# Sheet1.net
KiCad netlist of a schematic drawn in Altium Designer
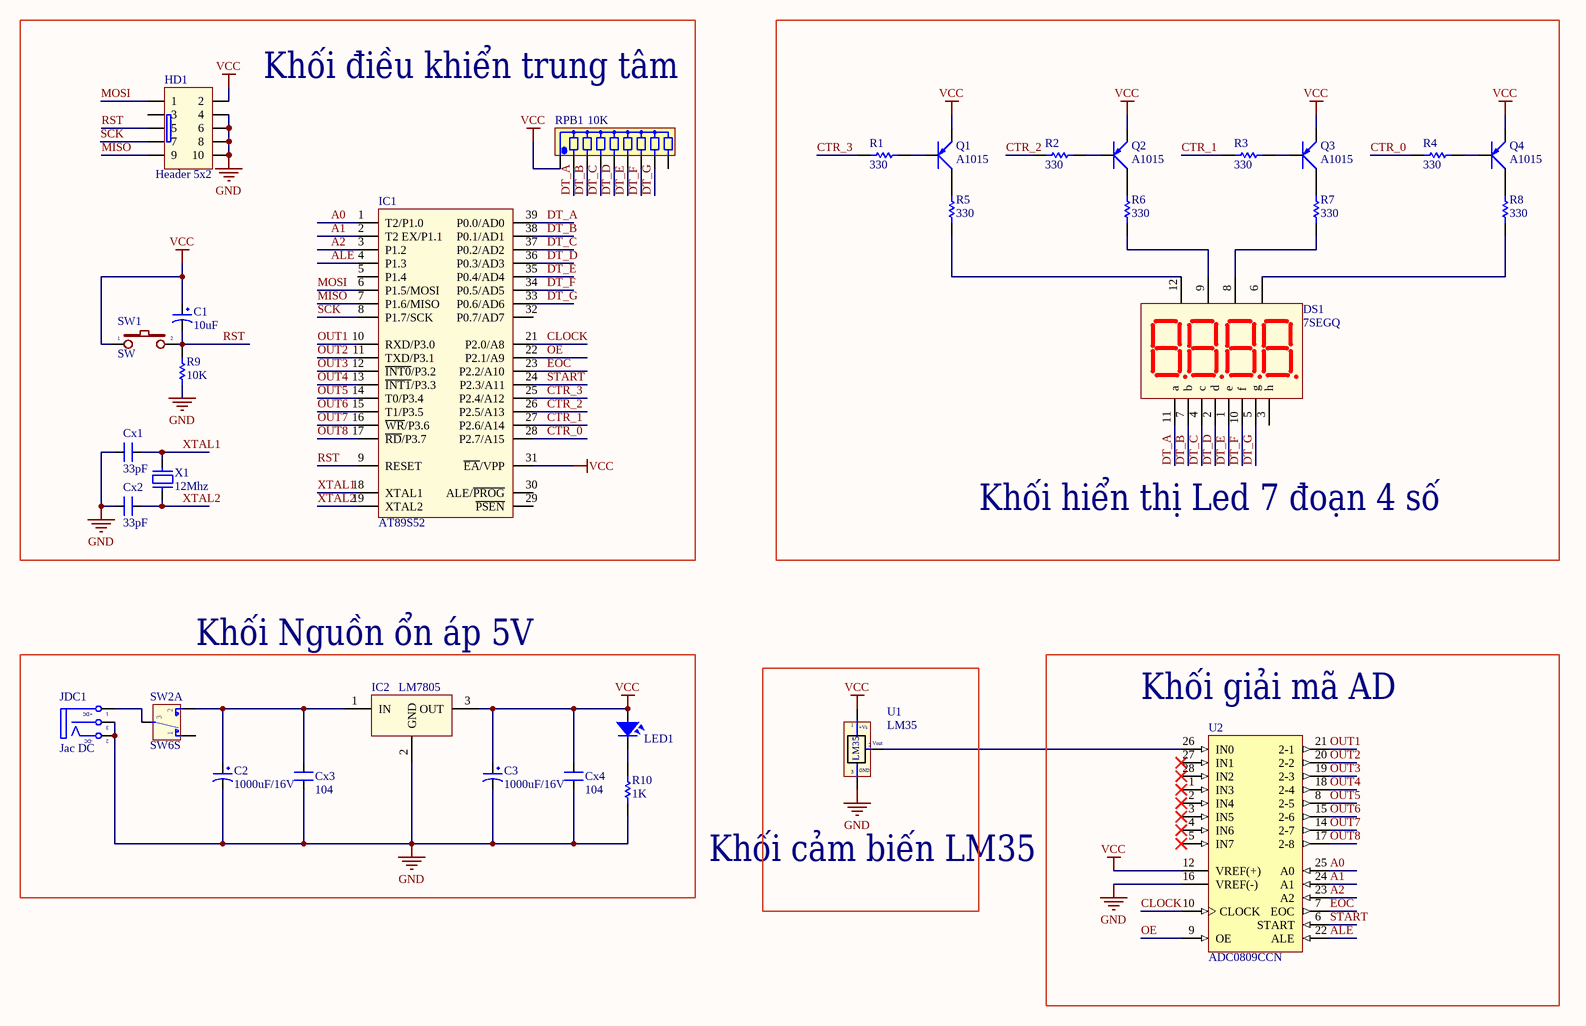
[diagram p0: Sheet1.SchDoc]

(export (version "E")
  (design (tool "Eeschema 10.0.6"))
  (components
    (comp (ref "C1")
      (value "10uF")
      (footprint "CP1/2")
      (description "Cap P  0,1uF < 22uF , 16 - 50V")
      (libsource (lib "DEV_lib") (part "Cap 0,1uF-{gt}22uF"))
    )
    (comp (ref "C2")
      (value "1000uF/16V")
      (footprint "CP1.5/3.4")
      (description "Cap 1000uF/16V - 220uF/50V")
      (libsource (lib "syhaunguyen") (part "CP4"))
    )
    (comp (ref "C3")
      (value "1000uF/16V")
      (footprint "CP1.5/3.4")
      (description "Cap 1000uF/16V - 220uF/50V")
      (libsource (lib "syhaunguyen") (part "CP4"))
    )
    (comp (ref "Cx1")
      (value "33pF")
      (footprint "CN1")
      (description "Cremic For Xtal 1pF => 100pF")
      (libsource (lib "syhaunguyen") (part "CN0"))
    )
    (comp (ref "Cx2")
      (value "33pF")
      (footprint "CN1")
      (description "Cremic For Xtal 1pF => 100pF")
      (libsource (lib "syhaunguyen") (part "CN0"))
    )
    (comp (ref "Cx3") (value "104") (footprint "CN1") (libsource (lib "LIBRARY") (part "CN")))
    (comp (ref "Cx4") (value "104") (footprint "CN1") (libsource (lib "LIBRARY") (part "CN")))
    (comp (ref "DS1")
      (value "7SEGQ")
      (footprint "LED7SEG-4-0.36")
      (description "Four 7 Seg Dipslay")
      (libsource (lib "DEV_lib") (part "LED7SEG-4"))
    )
    (comp (ref "HD1") (value "Header 5x2") (footprint "Hed2X5") (libsource (lib "DEV_lib") (part "HED5x2")))
    (comp (ref "IC1")
      (value "AT89S52")
      (footprint "DIP40/W0.6")
      (description "AT89S52, 8k Byte Flash Memory , 40 Pin")
      (libsource (lib "LIBRARY") (part "AT89S52"))
    )
    (comp (ref "IC2")
      (value "LM7805")
      (footprint "QTO-220")
      (description "On ap +, from + 5 to + 24VDC")
      (libsource (lib "DEV_lib") (part "LM78xx"))
    )
    (comp (ref "JDC1")
      (value "Jac DC")
      (footprint "DC-IN")
      (description "Jac DC input")
      (libsource (lib "syhaunguyen") (part "DCIN"))
    )
    (comp (ref "LED1")
      (value "LED")
      (footprint "LED-5-RED")
      (description "LED Single colour Green and Red")
      (libsource (lib "syhaunguyen") (part "LED"))
    )
    (comp (ref "Q1")
      (value "A1015")
      (footprint "QTO-92")
      (description "PNP 600mW, ECB")
      (libsource (lib "DEV_lib") (part "A1015"))
    )
    (comp (ref "Q2")
      (value "A1015")
      (footprint "QTO-92")
      (description "PNP 600mW, ECB")
      (libsource (lib "DEV_lib") (part "A1015"))
    )
    (comp (ref "Q3")
      (value "A1015")
      (footprint "QTO-92")
      (description "PNP 600mW, ECB")
      (libsource (lib "DEV_lib") (part "A1015"))
    )
    (comp (ref "Q4")
      (value "A1015")
      (footprint "QTO-92")
      (description "PNP 600mW, ECB")
      (libsource (lib "DEV_lib") (part "A1015"))
    )
    (comp (ref "R1")
      (value "330")
      (footprint "R1/4W")
      (description "Resistor")
      (fields
        (field (name "MANUFACTURER") "Generic Components")
        (field (name "Comment") "Res1")
        (field (name "PUBLISHER") "Altium Hobart Technology Centre")
      )
      (libsource (lib "DEV_lib") (part "Res1_4"))
    )
    (comp (ref "R2")
      (value "330")
      (footprint "R1/4W")
      (description "Resistor")
      (fields
        (field (name "MANUFACTURER") "Generic Components")
        (field (name "Comment") "Res1")
        (field (name "PUBLISHER") "Altium Hobart Technology Centre")
      )
      (libsource (lib "DEV_lib") (part "Res1_4"))
    )
    (comp (ref "R3")
      (value "330")
      (footprint "R1/4W")
      (description "Resistor")
      (fields
        (field (name "MANUFACTURER") "Generic Components")
        (field (name "Comment") "Res1")
        (field (name "PUBLISHER") "Altium Hobart Technology Centre")
      )
      (libsource (lib "DEV_lib") (part "Res1_4"))
    )
    (comp (ref "R4")
      (value "330")
      (footprint "R1/4W")
      (description "Resistor")
      (fields
        (field (name "MANUFACTURER") "Generic Components")
        (field (name "Comment") "Res1")
        (field (name "PUBLISHER") "Altium Hobart Technology Centre")
      )
      (libsource (lib "DEV_lib") (part "Res1_4"))
    )
    (comp (ref "R5")
      (value "330")
      (footprint "R1/4W")
      (description "Resistor")
      (fields
        (field (name "MANUFACTURER") "Generic Components")
        (field (name "Comment") "Res1")
        (field (name "PUBLISHER") "Altium Hobart Technology Centre")
      )
      (libsource (lib "DEV_lib") (part "Res1_4"))
    )
    (comp (ref "R6")
      (value "330")
      (footprint "R1/4W")
      (description "Resistor")
      (fields
        (field (name "MANUFACTURER") "Generic Components")
        (field (name "Comment") "Res1")
        (field (name "PUBLISHER") "Altium Hobart Technology Centre")
      )
      (libsource (lib "DEV_lib") (part "Res1_4"))
    )
    (comp (ref "R7")
      (value "330")
      (footprint "R1/4W")
      (description "Resistor")
      (fields
        (field (name "MANUFACTURER") "Generic Components")
        (field (name "Comment") "Res1")
        (field (name "PUBLISHER") "Altium Hobart Technology Centre")
      )
      (libsource (lib "DEV_lib") (part "Res1_4"))
    )
    (comp (ref "R8")
      (value "330")
      (footprint "R1/4W")
      (description "Resistor")
      (fields
        (field (name "MANUFACTURER") "Generic Components")
        (field (name "Comment") "Res1")
        (field (name "PUBLISHER") "Altium Hobart Technology Centre")
      )
      (libsource (lib "DEV_lib") (part "Res1_4"))
    )
    (comp (ref "R9")
      (value "10K")
      (footprint "R1/4W")
      (description "Resistor")
      (fields
        (field (name "MANUFACTURER") "Generic Components")
        (field (name "Comment") "Res1")
        (field (name "PUBLISHER") "Altium Hobart Technology Centre")
      )
      (libsource (lib "DEV_lib") (part "Res1_4"))
    )
    (comp (ref "R10")
      (value "1K")
      (footprint "R1/4W")
      (description "Resistor")
      (fields
        (field (name "MANUFACTURER") "Generic Components")
        (field (name "Comment") "Res1")
        (field (name "PUBLISHER") "Altium Hobart Technology Centre")
      )
      (libsource (lib "DEV_lib") (part "Res1_4"))
    )
    (comp (ref "RPB1")
      (value "10K")
      (footprint "RN8")
      (description "Resistor 8 (Thanh)")
      (libsource (lib "LIBRARY") (part "RN8"))
    )
    (comp (ref "SW1")
      (value "SW")
      (footprint "SW2")
      (description "Switch button 2 pin")
      (libsource (lib "syhaunguyen") (part "SW2"))
    )
    (comp (ref "SW2")
      (value "SW6S")
      (footprint "SW6")
      (description "SW-DTDP - 6 Pin")
      (libsource (lib "syhaunguyen") (part "SW6S"))
    )
    (comp (ref "U1")
      (value "LM35")
      (footprint "QTO-92")
      (description "Teminal")
      (libsource (lib "syhaunguyen") (part "LM35"))
    )
    (comp (ref "U2")
      (value "ADC0809CCN")
      (footprint "DIP28/W0.6")
      (description "8-bit Microprocessor Compatible A/D Converters With 8-Channel Multiplexer")
      (fields
        (field (name "MANUFACTURER") "National Semiconductor")
        (field (name "DIGIKEYPARTNUMBER") "ADC0809CCN-ND")
        (field (name "PUBLISHER") "Altium Limited")
      )
      (libsource (lib "LIBRARY") (part "ADC0809CCN"))
    )
    (comp (ref "X1")
      (value "12Mhz")
      (footprint "XT2")
      (description "Crystal, 32.768 KHz, -40 to 85 degC, 3.2 x 1.5 x 0.9 mm SMD")
      (libsource (lib "LIBRARY") (part "XT2"))
    )
  )
  (nets
    (net (code "1") (name "/A0") (class "Default")
      (node (ref "IC1") (pin "1") (pinfunction "T2/P1.0_1") (pintype "passive"))
      (node (ref "U2") (pin "25") (pinfunction "A0_25") (pintype "input"))
    )
    (net (code "2") (name "/A1") (class "Default")
      (node (ref "IC1") (pin "2") (pinfunction "T2_EX/P1.1_2") (pintype "passive"))
      (node (ref "U2") (pin "24") (pinfunction "A1_24") (pintype "input"))
    )
    (net (code "3") (name "/A2") (class "Default")
      (node (ref "IC1") (pin "3") (pinfunction "P1.2_3") (pintype "passive"))
      (node (ref "U2") (pin "23") (pinfunction "A2_23") (pintype "input"))
    )
    (net (code "4") (name "/ALE") (class "Default")
      (node (ref "IC1") (pin "4") (pinfunction "P1.3_4") (pintype "passive"))
      (node (ref "U2") (pin "22") (pinfunction "ALE_22") (pintype "input"))
    )
    (net (code "5") (name "/CLOCK") (class "Default")
      (node (ref "IC1") (pin "21") (pinfunction "P2.0/A8_21") (pintype "passive"))
      (node (ref "U2") (pin "10") (pinfunction "CLOCK_10") (pintype "input"))
    )
    (net (code "6") (name "/CTR_0") (class "Default")
      (node (ref "IC1") (pin "28") (pinfunction "P2.7/A15_28") (pintype "passive"))
      (node (ref "R4") (pin "2") (pinfunction "2_2") (pintype "passive"))
    )
    (net (code "7") (name "/CTR_1") (class "Default")
      (node (ref "IC1") (pin "27") (pinfunction "P2.6/A14_27") (pintype "passive"))
      (node (ref "R3") (pin "2") (pinfunction "2_2") (pintype "passive"))
    )
    (net (code "8") (name "/CTR_2") (class "Default")
      (node (ref "IC1") (pin "26") (pinfunction "P2.5/A13_26") (pintype "passive"))
      (node (ref "R2") (pin "2") (pinfunction "2_2") (pintype "passive"))
    )
    (net (code "9") (name "/CTR_3") (class "Default")
      (node (ref "IC1") (pin "25") (pinfunction "P2.4/A12_25") (pintype "passive"))
      (node (ref "R1") (pin "2") (pinfunction "2_2") (pintype "passive"))
    )
    (net (code "10") (name "/DT_A") (class "Default")
      (node (ref "DS1") (pin "11") (pinfunction "a_11") (pintype "passive"))
      (node (ref "IC1") (pin "39") (pinfunction "P0.0/AD0_39") (pintype "passive"))
      (node (ref "RPB1") (pin "2") (pinfunction "2_2") (pintype "passive"))
    )
    (net (code "11") (name "/DT_B") (class "Default")
      (node (ref "DS1") (pin "7") (pinfunction "b_7") (pintype "passive"))
      (node (ref "IC1") (pin "38") (pinfunction "P0.1/AD1_38") (pintype "passive"))
      (node (ref "RPB1") (pin "3") (pinfunction "3_3") (pintype "passive"))
    )
    (net (code "12") (name "/DT_C") (class "Default")
      (node (ref "DS1") (pin "4") (pinfunction "c_4") (pintype "passive"))
      (node (ref "IC1") (pin "37") (pinfunction "P0.2/AD2_37") (pintype "passive"))
      (node (ref "RPB1") (pin "4") (pinfunction "4_4") (pintype "passive"))
    )
    (net (code "13") (name "/DT_D") (class "Default")
      (node (ref "DS1") (pin "2") (pinfunction "d_2") (pintype "passive"))
      (node (ref "IC1") (pin "36") (pinfunction "P0.3/AD3_36") (pintype "passive"))
      (node (ref "RPB1") (pin "5") (pinfunction "5_5") (pintype "passive"))
    )
    (net (code "14") (name "/DT_E") (class "Default")
      (node (ref "DS1") (pin "1") (pinfunction "e_1") (pintype "passive"))
      (node (ref "IC1") (pin "35") (pinfunction "P0.4/AD4_35") (pintype "passive"))
      (node (ref "RPB1") (pin "6") (pinfunction "6_6") (pintype "passive"))
    )
    (net (code "15") (name "/DT_F") (class "Default")
      (node (ref "DS1") (pin "10") (pinfunction "f_10") (pintype "passive"))
      (node (ref "IC1") (pin "34") (pinfunction "P0.5/AD5_34") (pintype "passive"))
      (node (ref "RPB1") (pin "7") (pinfunction "7_7") (pintype "passive"))
    )
    (net (code "16") (name "/DT_G") (class "Default")
      (node (ref "DS1") (pin "5") (pinfunction "g_5") (pintype "passive"))
      (node (ref "IC1") (pin "33") (pinfunction "P0.6/AD6_33") (pintype "passive"))
      (node (ref "RPB1") (pin "8") (pinfunction "8_8") (pintype "passive"))
    )
    (net (code "17") (name "/EOC") (class "Default")
      (node (ref "IC1") (pin "23") (pinfunction "P2.2/A10_23") (pintype "passive"))
      (node (ref "U2") (pin "7") (pinfunction "EOC_7") (pintype "output"))
    )
    (net (code "18") (name "/MISO") (class "Default")
      (node (ref "HD1") (pin "9") (pinfunction "9_9") (pintype "passive"))
      (node (ref "IC1") (pin "7") (pinfunction "P1.6/MISO_7") (pintype "passive"))
    )
    (net (code "19") (name "/MOSI") (class "Default")
      (node (ref "HD1") (pin "1") (pinfunction "1_1") (pintype "passive"))
      (node (ref "IC1") (pin "6") (pinfunction "P1.5/MOSI_6") (pintype "passive"))
    )
    (net (code "20") (name "/OE") (class "Default")
      (node (ref "IC1") (pin "22") (pinfunction "P2.1/A9_22") (pintype "passive"))
      (node (ref "U2") (pin "9") (pinfunction "OE_9") (pintype "input"))
    )
    (net (code "21") (name "/OUT1") (class "Default")
      (node (ref "IC1") (pin "10") (pinfunction "RXD/P3.0_10") (pintype "passive"))
      (node (ref "U2") (pin "21") (pinfunction "2-1_21") (pintype "output"))
    )
    (net (code "22") (name "/OUT2") (class "Default")
      (node (ref "IC1") (pin "11") (pinfunction "TXD/P3.1_11") (pintype "passive"))
      (node (ref "U2") (pin "20") (pinfunction "2-2_20") (pintype "output"))
    )
    (net (code "23") (name "/OUT3") (class "Default")
      (node (ref "IC1") (pin "12") (pinfunction "~{INT0}/P3.2_12") (pintype "passive"))
      (node (ref "U2") (pin "19") (pinfunction "2-3_19") (pintype "output"))
    )
    (net (code "24") (name "/OUT4") (class "Default")
      (node (ref "IC1") (pin "13") (pinfunction "~{INT1}/P3.3_13") (pintype "passive"))
      (node (ref "U2") (pin "18") (pinfunction "2-4_18") (pintype "output"))
    )
    (net (code "25") (name "/OUT5") (class "Default")
      (node (ref "IC1") (pin "14") (pinfunction "T0/P3.4_14") (pintype "passive"))
      (node (ref "U2") (pin "8") (pinfunction "2-5_8") (pintype "output"))
    )
    (net (code "26") (name "/OUT6") (class "Default")
      (node (ref "IC1") (pin "15") (pinfunction "T1/P3.5_15") (pintype "passive"))
      (node (ref "U2") (pin "15") (pinfunction "2-6_15") (pintype "output"))
    )
    (net (code "27") (name "/OUT7") (class "Default")
      (node (ref "IC1") (pin "16") (pinfunction "~{WR}/P3.6_16") (pintype "passive"))
      (node (ref "U2") (pin "14") (pinfunction "2-7_14") (pintype "output"))
    )
    (net (code "28") (name "/OUT8") (class "Default")
      (node (ref "IC1") (pin "17") (pinfunction "~{RD}/P3.7_17") (pintype "passive"))
      (node (ref "U2") (pin "17") (pinfunction "2-8_17") (pintype "output"))
    )
    (net (code "29") (name "/RST") (class "Default")
      (node (ref "C1") (pin "2") (pinfunction "2_2") (pintype "passive"))
      (node (ref "HD1") (pin "5") (pinfunction "5_5") (pintype "passive"))
      (node (ref "IC1") (pin "9") (pinfunction "RESET_9") (pintype "passive"))
      (node (ref "R9") (pin "1") (pinfunction "1_1") (pintype "passive"))
      (node (ref "SW1") (pin "2") (pinfunction "2_2") (pintype "passive"))
    )
    (net (code "30") (name "/SCK") (class "Default")
      (node (ref "HD1") (pin "7") (pinfunction "7_7") (pintype "passive"))
      (node (ref "IC1") (pin "8") (pinfunction "P1.7/SCK_8") (pintype "passive"))
    )
    (net (code "31") (name "/START") (class "Default")
      (node (ref "IC1") (pin "24") (pinfunction "P2.3/A11_24") (pintype "passive"))
      (node (ref "U2") (pin "6") (pinfunction "START_6") (pintype "input"))
    )
    (net (code "32") (name "/XTAL1") (class "Default")
      (node (ref "Cx1") (pin "2") (pinfunction "2_2") (pintype "passive"))
      (node (ref "IC1") (pin "18") (pinfunction "XTAL1_18") (pintype "passive"))
      (node (ref "X1") (pin "2") (pinfunction "2_2") (pintype "passive"))
    )
    (net (code "33") (name "/XTAL2") (class "Default")
      (node (ref "Cx2") (pin "2") (pinfunction "2_2") (pintype "passive"))
      (node (ref "IC1") (pin "19") (pinfunction "XTAL2_19") (pintype "passive"))
      (node (ref "X1") (pin "1") (pinfunction "1_1") (pintype "passive"))
    )
    (net (code "34") (name "GND") (class "Default")
      (node (ref "C2") (pin "2") (pinfunction "2_2") (pintype "passive"))
      (node (ref "C3") (pin "2") (pinfunction "2_2") (pintype "passive"))
      (node (ref "Cx1") (pin "1") (pinfunction "1_1") (pintype "passive"))
      (node (ref "Cx2") (pin "1") (pinfunction "1_1") (pintype "passive"))
      (node (ref "Cx3") (pin "1") (pinfunction "1_1") (pintype "passive"))
      (node (ref "Cx4") (pin "1") (pinfunction "1_1") (pintype "passive"))
      (node (ref "HD1") (pin "10") (pinfunction "10_10") (pintype "passive"))
      (node (ref "HD1") (pin "4") (pinfunction "4_4") (pintype "passive"))
      (node (ref "HD1") (pin "6") (pinfunction "6_6") (pintype "passive"))
      (node (ref "HD1") (pin "8") (pinfunction "8_8") (pintype "passive"))
      (node (ref "IC1") (pin "20") (pinfunction "GND_20") (pintype "power_in"))
      (node (ref "IC2") (pin "2") (pinfunction "GND_2") (pintype "passive"))
      (node (ref "JDC1") (pin "2") (pinfunction "TN_2") (pintype "passive"))
      (node (ref "JDC1") (pin "3") (pinfunction "S_3") (pintype "power_in"))
      (node (ref "R10") (pin "1") (pinfunction "1_1") (pintype "passive"))
      (node (ref "R9") (pin "2") (pinfunction "2_2") (pintype "passive"))
      (node (ref "U1") (pin "3") (pinfunction "-_3") (pintype "passive"))
      (node (ref "U2") (pin "13") (pinfunction "GND_13") (pintype "power_in"))
      (node (ref "U2") (pin "16") (pinfunction "VREF(-)_16") (pintype "power_in"))
    )
    (net (code "35") (name "Net-(DS1-V1)") (class "Default")
      (node (ref "DS1") (pin "12") (pinfunction "V1_12") (pintype "passive"))
      (node (ref "R5") (pin "1") (pinfunction "1_1") (pintype "passive"))
    )
    (net (code "36") (name "Net-(DS1-V2)") (class "Default")
      (node (ref "DS1") (pin "9") (pinfunction "V2_9") (pintype "passive"))
      (node (ref "R6") (pin "1") (pinfunction "1_1") (pintype "passive"))
    )
    (net (code "37") (name "Net-(DS1-V3)") (class "Default")
      (node (ref "DS1") (pin "8") (pinfunction "V3_8") (pintype "passive"))
      (node (ref "R7") (pin "1") (pinfunction "1_1") (pintype "passive"))
    )
    (net (code "38") (name "Net-(DS1-V4)") (class "Default")
      (node (ref "DS1") (pin "6") (pinfunction "V4_6") (pintype "passive"))
      (node (ref "R8") (pin "1") (pinfunction "1_1") (pintype "passive"))
    )
    (net (code "39") (name "Net-(IC2-IN)") (class "Default")
      (node (ref "C2") (pin "1") (pinfunction "1_1") (pintype "passive"))
      (node (ref "Cx3") (pin "2") (pinfunction "2_2") (pintype "passive"))
      (node (ref "IC2") (pin "1") (pinfunction "IN_1") (pintype "passive"))
      (node (ref "SW2") (pin "2") (pinfunction "2_2") (pintype "passive"))
    )
    (net (code "40") (name "Net-(JDC1-T)") (class "Default")
      (node (ref "JDC1") (pin "1") (pinfunction "T_1") (pintype "passive"))
      (node (ref "SW2") (pin "3") (pinfunction "3_3") (pintype "passive"))
    )
    (net (code "41") (name "Net-(LED1-Pad2)") (class "Default")
      (node (ref "LED1") (pin "2") (pinfunction "2_2") (pintype "passive"))
      (node (ref "R10") (pin "2") (pinfunction "2_2") (pintype "passive"))
    )
    (net (code "42") (name "Net-(Q1-B)") (class "Default")
      (node (ref "Q1") (pin "3") (pinfunction "B_3") (pintype "passive"))
      (node (ref "R1") (pin "1") (pinfunction "1_1") (pintype "passive"))
    )
    (net (code "43") (name "Net-(Q1-C)") (class "Default")
      (node (ref "Q1") (pin "2") (pinfunction "C_2") (pintype "passive"))
      (node (ref "R5") (pin "2") (pinfunction "2_2") (pintype "passive"))
    )
    (net (code "44") (name "Net-(Q2-B)") (class "Default")
      (node (ref "Q2") (pin "3") (pinfunction "B_3") (pintype "passive"))
      (node (ref "R2") (pin "1") (pinfunction "1_1") (pintype "passive"))
    )
    (net (code "45") (name "Net-(Q2-C)") (class "Default")
      (node (ref "Q2") (pin "2") (pinfunction "C_2") (pintype "passive"))
      (node (ref "R6") (pin "2") (pinfunction "2_2") (pintype "passive"))
    )
    (net (code "46") (name "Net-(Q3-B)") (class "Default")
      (node (ref "Q3") (pin "3") (pinfunction "B_3") (pintype "passive"))
      (node (ref "R3") (pin "1") (pinfunction "1_1") (pintype "passive"))
    )
    (net (code "47") (name "Net-(Q3-C)") (class "Default")
      (node (ref "Q3") (pin "2") (pinfunction "C_2") (pintype "passive"))
      (node (ref "R7") (pin "2") (pinfunction "2_2") (pintype "passive"))
    )
    (net (code "48") (name "Net-(Q4-B)") (class "Default")
      (node (ref "Q4") (pin "3") (pinfunction "B_3") (pintype "passive"))
      (node (ref "R4") (pin "1") (pinfunction "1_1") (pintype "passive"))
    )
    (net (code "49") (name "Net-(Q4-C)") (class "Default")
      (node (ref "Q4") (pin "2") (pinfunction "C_2") (pintype "passive"))
      (node (ref "R8") (pin "2") (pinfunction "2_2") (pintype "passive"))
    )
    (net (code "50") (name "Net-(U1-Vout)") (class "Default")
      (node (ref "U1") (pin "2") (pinfunction "Vout_2") (pintype "passive"))
      (node (ref "U2") (pin "26") (pinfunction "IN0_26") (pintype "input"))
    )
    (net (code "51") (name "VCC") (class "Default")
      (node (ref "C1") (pin "1") (pinfunction "1_1") (pintype "passive"))
      (node (ref "C3") (pin "1") (pinfunction "1_1") (pintype "passive"))
      (node (ref "Cx4") (pin "2") (pinfunction "2_2") (pintype "passive"))
      (node (ref "HD1") (pin "2") (pinfunction "2_2") (pintype "passive"))
      (node (ref "IC1") (pin "31") (pinfunction "~{EA}/VPP_31") (pintype "passive"))
      (node (ref "IC1") (pin "40") (pinfunction "VCC_40") (pintype "power_in"))
      (node (ref "IC2") (pin "3") (pinfunction "OUT_3") (pintype "passive"))
      (node (ref "LED1") (pin "1") (pinfunction "1_1") (pintype "passive"))
      (node (ref "Q1") (pin "1") (pinfunction "E_1") (pintype "passive"))
      (node (ref "Q2") (pin "1") (pinfunction "E_1") (pintype "passive"))
      (node (ref "Q3") (pin "1") (pinfunction "E_1") (pintype "passive"))
      (node (ref "Q4") (pin "1") (pinfunction "E_1") (pintype "passive"))
      (node (ref "RPB1") (pin "1") (pinfunction "1_1") (pintype "passive"))
      (node (ref "SW1") (pin "1") (pinfunction "1_1") (pintype "passive"))
      (node (ref "U1") (pin "1") (pinfunction "+Vs_1") (pintype "passive"))
      (node (ref "U2") (pin "11") (pinfunction "VCC_11") (pintype "power_in"))
      (node (ref "U2") (pin "12") (pinfunction "VREF(+)_12") (pintype "power_in"))
    )
    (net (code "52") (name "unconnected-(DS1-h-Pad3)") (class "Default")
      (node (ref "DS1") (pin "3") (pinfunction "h_3") (pintype "passive"))
    )
    (net (code "53") (name "unconnected-(HD1-Pad3)") (class "Default")
      (node (ref "HD1") (pin "3") (pinfunction "3_3") (pintype "passive"))
    )
    (net (code "54") (name "unconnected-(IC1-ALE{slash}~{PROG}-Pad30)") (class "Default")
      (node (ref "IC1") (pin "30") (pinfunction "ALE/~{PROG}_30") (pintype "passive"))
    )
    (net (code "55") (name "unconnected-(IC1-P0.7{slash}AD7-Pad32)") (class "Default")
      (node (ref "IC1") (pin "32") (pinfunction "P0.7/AD7_32") (pintype "passive"))
    )
    (net (code "56") (name "unconnected-(IC1-P1.4-Pad5)") (class "Default")
      (node (ref "IC1") (pin "5") (pinfunction "P1.4_5") (pintype "passive"))
    )
    (net (code "57") (name "unconnected-(IC1-~{PSEN}-Pad29)") (class "Default")
      (node (ref "IC1") (pin "29") (pinfunction "~{PSEN}_29") (pintype "passive"))
    )
    (net (code "58") (name "unconnected-(RPB1-Pad9)") (class "Default")
      (node (ref "RPB1") (pin "9") (pinfunction "9_9") (pintype "passive"))
    )
    (net (code "59") (name "unconnected-(SW2-Pad1)") (class "Default")
      (node (ref "SW2") (pin "1") (pinfunction "1_1") (pintype "passive"))
    )
    (net (code "60") (name "unconnected-(U2-IN1-Pad27)") (class "Default")
      (node (ref "U2") (pin "27") (pinfunction "IN1_27") (pintype "input+no_connect"))
    )
    (net (code "61") (name "unconnected-(U2-IN2-Pad28)") (class "Default")
      (node (ref "U2") (pin "28") (pinfunction "IN2_28") (pintype "input+no_connect"))
    )
    (net (code "62") (name "unconnected-(U2-IN3-Pad1)") (class "Default")
      (node (ref "U2") (pin "1") (pinfunction "IN3_1") (pintype "input+no_connect"))
    )
    (net (code "63") (name "unconnected-(U2-IN4-Pad2)") (class "Default")
      (node (ref "U2") (pin "2") (pinfunction "IN4_2") (pintype "input+no_connect"))
    )
    (net (code "64") (name "unconnected-(U2-IN5-Pad3)") (class "Default")
      (node (ref "U2") (pin "3") (pinfunction "IN5_3") (pintype "input+no_connect"))
    )
    (net (code "65") (name "unconnected-(U2-IN6-Pad4)") (class "Default")
      (node (ref "U2") (pin "4") (pinfunction "IN6_4") (pintype "input+no_connect"))
    )
    (net (code "66") (name "unconnected-(U2-IN7-Pad5)") (class "Default")
      (node (ref "U2") (pin "5") (pinfunction "IN7_5") (pintype "input+no_connect"))
    )
  )
)
